# Hpowerv2.net
KiCad netlist of a schematic drawn in Altium Designer
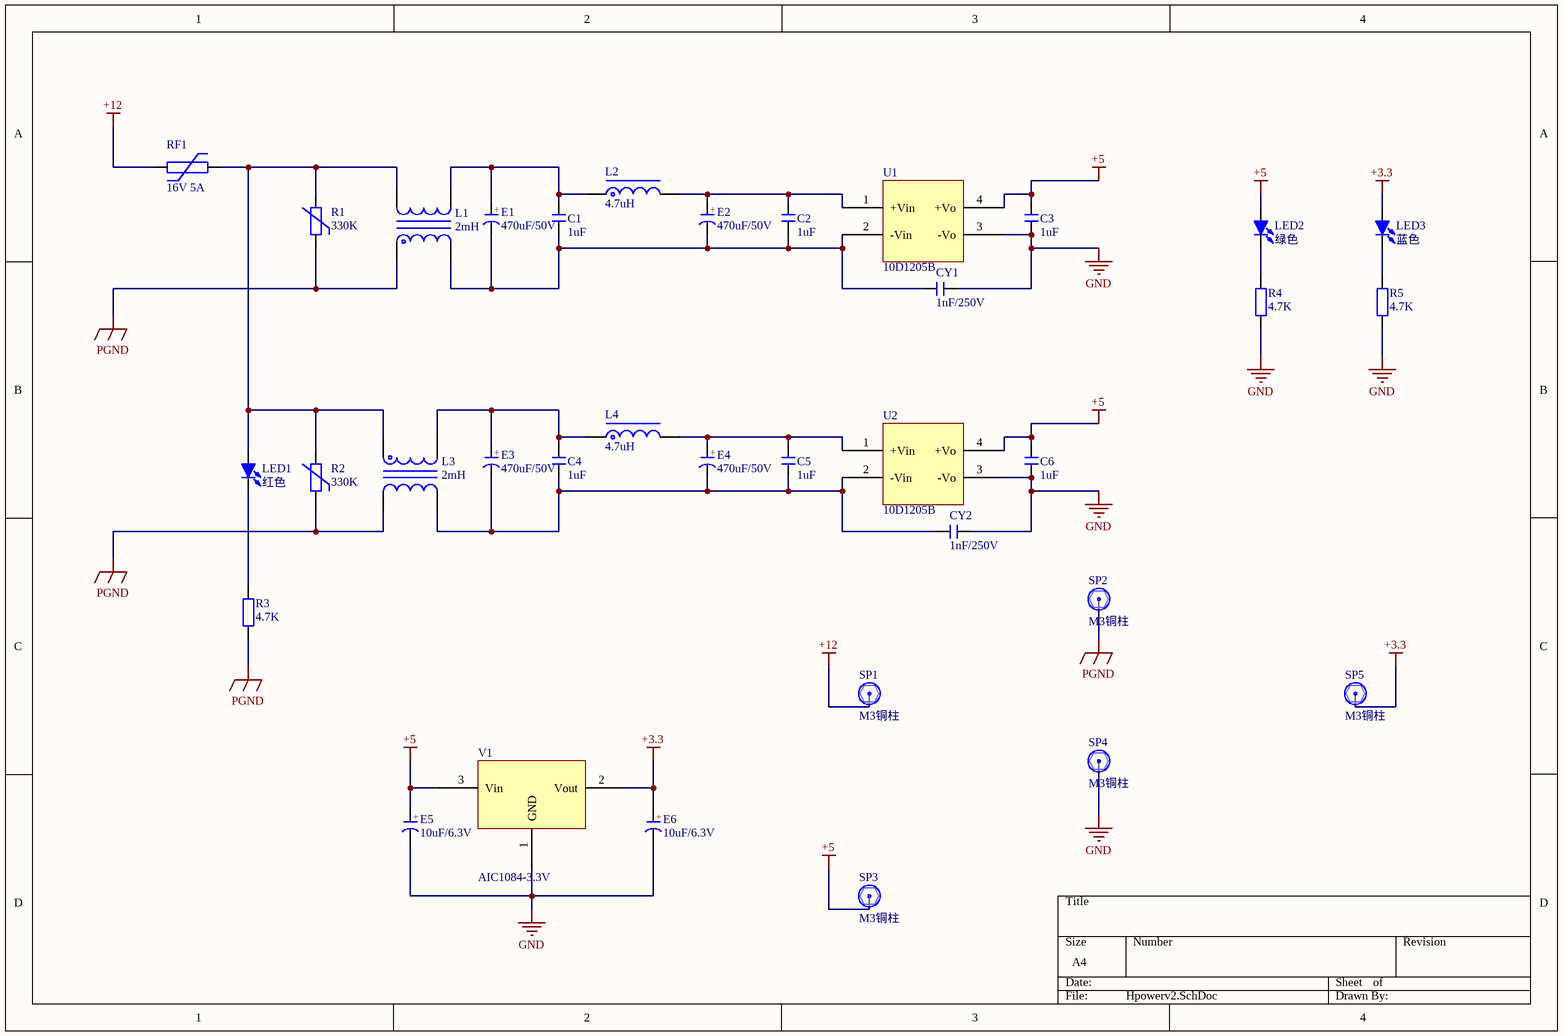
[diagram p0: Hpowerv2.SchDoc]

(export (version "E")
  (design (tool "Eeschema 10.0.6"))
  (components
    (comp (ref "C1")
      (value "1uF")
      (footprint "CC 2.2*5")
      (description "直插瓷片电容")
      (fields (field (name "版权归属") "源创客"))
      (libsource (lib "3.1   - 电阻-电容-电感") (part "C-CC"))
    )
    (comp (ref "C2")
      (value "1uF")
      (footprint "CC 2.2*5")
      (description "直插瓷片电容")
      (fields (field (name "版权归属") "源创客"))
      (libsource (lib "3.1   - 电阻-电容-电感") (part "C-CC"))
    )
    (comp (ref "C3")
      (value "1uF")
      (footprint "CC 2.2*5")
      (description "直插瓷片电容")
      (fields (field (name "版权归属") "源创客"))
      (libsource (lib "3.1   - 电阻-电容-电感") (part "C-CC"))
    )
    (comp (ref "C4")
      (value "1uF")
      (footprint "CC 2.2*5")
      (description "直插瓷片电容")
      (fields (field (name "版权归属") "源创客"))
      (libsource (lib "3.1   - 电阻-电容-电感") (part "C-CC"))
    )
    (comp (ref "C5")
      (value "1uF")
      (footprint "CC 2.2*5")
      (description "直插瓷片电容")
      (fields (field (name "版权归属") "源创客"))
      (libsource (lib "3.1   - 电阻-电容-电感") (part "C-CC"))
    )
    (comp (ref "C6")
      (value "1uF")
      (footprint "CC 2.2*5")
      (description "直插瓷片电容")
      (fields (field (name "版权归属") "源创客"))
      (libsource (lib "3.1   - 电阻-电容-电感") (part "C-CC"))
    )
    (comp (ref "CY1")
      (value "1nF/250V")
      (footprint "CY 7.5*10*4")
      (description "高压陶瓷电容，Y电容")
      (fields (field (name "版权归属") "源创客"))
      (libsource (lib "3.1   - 电阻-电容-电感") (part "C-CY"))
    )
    (comp (ref "CY2")
      (value "1nF/250V")
      (footprint "CY 7.5*10*4")
      (description "高压陶瓷电容，Y电容")
      (fields (field (name "版权归属") "源创客"))
      (libsource (lib "3.1   - 电阻-电容-电感") (part "C-CY"))
    )
    (comp (ref "E1")
      (value "470uF/50V")
      (footprint "CM G(12.5*13.5)")
      (description "贴片电解电容")
      (fields (field (name "版权归属") "源创客"))
      (libsource (lib "3.1   - 电阻-电容-电感") (part "C-CM"))
    )
    (comp (ref "E2")
      (value "470uF/50V")
      (footprint "CM G(12.5*13.5)")
      (description "贴片电解电容")
      (fields (field (name "版权归属") "源创客"))
      (libsource (lib "3.1   - 电阻-电容-电感") (part "C-CM"))
    )
    (comp (ref "E3")
      (value "470uF/50V")
      (footprint "CM G(12.5*13.5)")
      (description "贴片电解电容")
      (fields (field (name "版权归属") "源创客"))
      (libsource (lib "3.1   - 电阻-电容-电感") (part "C-CM"))
    )
    (comp (ref "E4")
      (value "470uF/50V")
      (footprint "CM G(12.5*13.5)")
      (description "贴片电解电容")
      (fields (field (name "版权归属") "源创客"))
      (libsource (lib "3.1   - 电阻-电容-电感") (part "C-CM"))
    )
    (comp (ref "E5")
      (value "10uF/6.3V")
      (footprint "CD A(3216)")
      (description "贴片钽电容")
      (fields (field (name "版权归属") "源创客"))
      (libsource (lib "3.1   - 电阻-电容-电感") (part "C-CD"))
    )
    (comp (ref "E6")
      (value "10uF/6.3V")
      (footprint "CD A(3216)")
      (description "贴片钽电容")
      (fields (field (name "版权归属") "源创客"))
      (libsource (lib "3.1   - 电阻-电容-电感") (part "C-CD"))
    )
    (comp (ref "L1")
      (value "2mH")
      (footprint "UU9.8")
      (description "共模电感")
      (fields (field (name "版权归属") "源创客"))
      (libsource (lib "") (part "L-CMC_1"))
    )
    (comp (ref "L2")
      (value "4.7uH")
      (footprint "NR5020")
      (description "NR磁胶电感")
      (fields (field (name "版权归属") "源创客"))
      (libsource (lib "3.1   - 电阻-电容-电感") (part "L-NR"))
    )
    (comp (ref "L3")
      (value "2mH")
      (footprint "UU9.8")
      (description "共模电感")
      (fields (field (name "版权归属") "源创客"))
      (libsource (lib "3.1   - 电阻-电容-电感") (part "L-CMC"))
    )
    (comp (ref "L4")
      (value "4.7uH")
      (footprint "NR5020")
      (description "NR磁胶电感")
      (fields (field (name "版权归属") "源创客"))
      (libsource (lib "3.1   - 电阻-电容-电感") (part "L-NR"))
    )
    (comp (ref "LED1")
      (value "红色")
      (footprint "LED 0603R")
      (description "贴片LED")
      (fields (field (name "版权归属") "源创客"))
      (libsource (lib "9.1   - LED") (part "LED-SMD"))
    )
    (comp (ref "LED2")
      (value "绿色")
      (footprint "LED 0603G")
      (description "贴片LED")
      (fields (field (name "版权归属") "源创客"))
      (libsource (lib "9.1   - LED") (part "LED-SMD"))
    )
    (comp (ref "LED3")
      (value "蓝色")
      (footprint "LED 0603B")
      (description "贴片LED")
      (fields (field (name "版权归属") "源创客"))
      (libsource (lib "9.1   - LED") (part "LED-SMD"))
    )
    (comp (ref "R1")
      (value "330K")
      (footprint "14D")
      (description "压敏电阻")
      (fields (field (name "版权归属") "源创客"))
      (libsource (lib "3.1   - 电阻-电容-电感") (part "R_VDR"))
    )
    (comp (ref "R2")
      (value "330K")
      (footprint "14D")
      (description "压敏电阻")
      (fields (field (name "版权归属") "源创客"))
      (libsource (lib "3.1   - 电阻-电容-电感") (part "R_VDR"))
    )
    (comp (ref "R3")
      (value "4.7K")
      (footprint "R 0603_M")
      (description "贴片电阻")
      (fields (field (name "版权归属") "源创客"))
      (libsource (lib "3.1   - 电阻-电容-电感") (part "R"))
    )
    (comp (ref "R4")
      (value "4.7K")
      (footprint "R 0603_M")
      (description "贴片电阻")
      (fields (field (name "版权归属") "源创客"))
      (libsource (lib "3.1   - 电阻-电容-电感") (part "R"))
    )
    (comp (ref "R5")
      (value "4.7K")
      (footprint "R 0603_M")
      (description "贴片电阻")
      (fields (field (name "版权归属") "源创客"))
      (libsource (lib "3.1   - 电阻-电容-电感") (part "R"))
    )
    (comp (ref "RF1")
      (value "16V 5A")
      (footprint "14D")
      (description "PPTC自恢复保险丝")
      (fields (field (name "版权归属") "源创客"))
      (libsource (lib "10.1 - 保险丝-晶振") (part "PPTC"))
    )
    (comp (ref "SP1")
      (value "M3铜柱")
      (footprint "M3x14_N")
      (description "铜柱")
      (fields (field (name "版权归属") "源创客"))
      (libsource (lib "15.1 - 未分类器件") (part "铜柱大焊盘"))
    )
    (comp (ref "SP2")
      (value "M3铜柱")
      (footprint "M3x14_N")
      (description "铜柱")
      (fields (field (name "版权归属") "源创客"))
      (libsource (lib "15.1 - 未分类器件") (part "铜柱大焊盘"))
    )
    (comp (ref "SP3")
      (value "M3铜柱")
      (footprint "M3x14_N")
      (description "铜柱")
      (fields (field (name "版权归属") "源创客"))
      (libsource (lib "15.1 - 未分类器件") (part "铜柱大焊盘"))
    )
    (comp (ref "SP4")
      (value "M3铜柱")
      (footprint "M3x14_N")
      (description "铜柱")
      (fields (field (name "版权归属") "源创客"))
      (libsource (lib "15.1 - 未分类器件") (part "铜柱大焊盘"))
    )
    (comp (ref "SP5")
      (value "M3铜柱")
      (footprint "M3x14_N")
      (description "铜柱")
      (fields (field (name "版权归属") "源创客"))
      (libsource (lib "15.1 - 未分类器件") (part "铜柱大焊盘"))
    )
    (comp (ref "U1")
      (value "10D1205B")
      (footprint "10D12B-10WDCDC")
      (description "DC-DC 12V转5V隔离降压模块")
      (libsource (lib "HLKPower") (part "10D1205B"))
    )
    (comp (ref "U2")
      (value "10D1205B")
      (footprint "10D12B-10WDCDC")
      (description "DC-DC 12V转5V隔离降压模块")
      (libsource (lib "HLKPower") (part "10D1205B"))
    )
    (comp (ref "V1")
      (value "AIC1084-3.3V")
      (footprint "TO263-3B")
      (description "大功率LDO")
      (libsource (lib "1.3   - 电源类芯片") (part "AIC1084"))
    )
  )
  (nets
    (net (code "1") (name "+3.3") (class "Default")
      (node (ref "E6") (pin "1") (pinfunction "A_1") (pintype "passive"))
      (node (ref "LED3") (pin "1") (pinfunction "A_1") (pintype "passive"))
      (node (ref "SP5") (pin "1") (pinfunction "1_1") (pintype "passive"))
      (node (ref "V1") (pin "2") (pinfunction "Vout_2") (pintype "passive"))
    )
    (net (code "2") (name "+5") (class "Default")
      (node (ref "C3") (pin "1") (pinfunction "1_1") (pintype "passive"))
      (node (ref "C6") (pin "1") (pinfunction "1_1") (pintype "passive"))
      (node (ref "E5") (pin "1") (pinfunction "A_1") (pintype "passive"))
      (node (ref "LED2") (pin "1") (pinfunction "A_1") (pintype "passive"))
      (node (ref "SP3") (pin "1") (pinfunction "1_1") (pintype "passive"))
      (node (ref "U1") (pin "4") (pinfunction "+Vo_4") (pintype "passive"))
      (node (ref "U2") (pin "4") (pinfunction "+Vo_4") (pintype "passive"))
      (node (ref "V1") (pin "3") (pinfunction "Vin_3") (pintype "passive"))
    )
    (net (code "3") (name "+12") (class "Default")
      (node (ref "RF1") (pin "1") (pinfunction "1_1") (pintype "passive"))
      (node (ref "SP1") (pin "1") (pinfunction "1_1") (pintype "passive"))
    )
    (net (code "4") (name "GND") (class "Default")
      (node (ref "C3") (pin "2") (pinfunction "2_2") (pintype "passive"))
      (node (ref "C6") (pin "2") (pinfunction "2_2") (pintype "passive"))
      (node (ref "CY1") (pin "2") (pinfunction "2_2") (pintype "passive"))
      (node (ref "CY2") (pin "2") (pinfunction "2_2") (pintype "passive"))
      (node (ref "E5") (pin "2") (pinfunction "K_2") (pintype "passive"))
      (node (ref "E6") (pin "2") (pinfunction "K_2") (pintype "passive"))
      (node (ref "R4") (pin "1") (pinfunction "1_1") (pintype "passive"))
      (node (ref "R5") (pin "1") (pinfunction "1_1") (pintype "passive"))
      (node (ref "SP4") (pin "1") (pinfunction "1_1") (pintype "passive"))
      (node (ref "U1") (pin "3") (pinfunction "-Vo_3") (pintype "passive"))
      (node (ref "U2") (pin "3") (pinfunction "-Vo_3") (pintype "passive"))
      (node (ref "V1") (pin "1") (pinfunction "GND_1") (pintype "passive"))
    )
    (net (code "5") (name "Net-(E1-A)") (class "Default")
      (node (ref "C1") (pin "1") (pinfunction "1_1") (pintype "passive"))
      (node (ref "E1") (pin "1") (pinfunction "A_1") (pintype "passive"))
      (node (ref "L1") (pin "3") (pinfunction "3_3") (pintype "passive"))
      (node (ref "L2") (pin "1") (pinfunction "1_1") (pintype "passive"))
    )
    (net (code "6") (name "Net-(E1-K)") (class "Default")
      (node (ref "C1") (pin "2") (pinfunction "2_2") (pintype "passive"))
      (node (ref "C2") (pin "2") (pinfunction "2_2") (pintype "passive"))
      (node (ref "CY1") (pin "1") (pinfunction "1_1") (pintype "passive"))
      (node (ref "E1") (pin "2") (pinfunction "K_2") (pintype "passive"))
      (node (ref "E2") (pin "2") (pinfunction "K_2") (pintype "passive"))
      (node (ref "L1") (pin "2") (pinfunction "2_2") (pintype "passive"))
      (node (ref "U1") (pin "2") (pinfunction "-Vin_2") (pintype "passive"))
    )
    (net (code "7") (name "Net-(E2-A)") (class "Default")
      (node (ref "C2") (pin "1") (pinfunction "1_1") (pintype "passive"))
      (node (ref "E2") (pin "1") (pinfunction "A_1") (pintype "passive"))
      (node (ref "L2") (pin "2") (pinfunction "2_2") (pintype "passive"))
      (node (ref "U1") (pin "1") (pinfunction "+Vin_1") (pintype "passive"))
    )
    (net (code "8") (name "Net-(E3-A)") (class "Default")
      (node (ref "C4") (pin "1") (pinfunction "1_1") (pintype "passive"))
      (node (ref "E3") (pin "1") (pinfunction "A_1") (pintype "passive"))
      (node (ref "L3") (pin "2") (pinfunction "2_2") (pintype "passive"))
      (node (ref "L4") (pin "1") (pinfunction "1_1") (pintype "passive"))
    )
    (net (code "9") (name "Net-(E3-K)") (class "Default")
      (node (ref "C4") (pin "2") (pinfunction "2_2") (pintype "passive"))
      (node (ref "C5") (pin "2") (pinfunction "2_2") (pintype "passive"))
      (node (ref "CY2") (pin "1") (pinfunction "1_1") (pintype "passive"))
      (node (ref "E3") (pin "2") (pinfunction "K_2") (pintype "passive"))
      (node (ref "E4") (pin "2") (pinfunction "K_2") (pintype "passive"))
      (node (ref "L3") (pin "3") (pinfunction "3_3") (pintype "passive"))
      (node (ref "U2") (pin "2") (pinfunction "-Vin_2") (pintype "passive"))
    )
    (net (code "10") (name "Net-(E4-A)") (class "Default")
      (node (ref "C5") (pin "1") (pinfunction "1_1") (pintype "passive"))
      (node (ref "E4") (pin "1") (pinfunction "A_1") (pintype "passive"))
      (node (ref "L4") (pin "2") (pinfunction "2_2") (pintype "passive"))
      (node (ref "U2") (pin "1") (pinfunction "+Vin_1") (pintype "passive"))
    )
    (net (code "11") (name "Net-(LED1-A)") (class "Default")
      (node (ref "L1") (pin "4") (pinfunction "4_4") (pintype "passive"))
      (node (ref "L3") (pin "1") (pinfunction "1_1") (pintype "passive"))
      (node (ref "LED1") (pin "1") (pinfunction "A_1") (pintype "passive"))
      (node (ref "R1") (pin "2") (pinfunction "2_2") (pintype "passive"))
      (node (ref "R2") (pin "2") (pinfunction "2_2") (pintype "passive"))
      (node (ref "RF1") (pin "2") (pinfunction "2_2") (pintype "passive"))
    )
    (net (code "12") (name "Net-(LED1-K)") (class "Default")
      (node (ref "LED1") (pin "2") (pinfunction "K_2") (pintype "passive"))
      (node (ref "R3") (pin "2") (pinfunction "2_2") (pintype "passive"))
    )
    (net (code "13") (name "Net-(LED2-K)") (class "Default")
      (node (ref "LED2") (pin "2") (pinfunction "K_2") (pintype "passive"))
      (node (ref "R4") (pin "2") (pinfunction "2_2") (pintype "passive"))
    )
    (net (code "14") (name "Net-(LED3-K)") (class "Default")
      (node (ref "LED3") (pin "2") (pinfunction "K_2") (pintype "passive"))
      (node (ref "R5") (pin "2") (pinfunction "2_2") (pintype "passive"))
    )
    (net (code "15") (name "PGND") (class "Default")
      (node (ref "L1") (pin "1") (pinfunction "1_1") (pintype "passive"))
      (node (ref "L3") (pin "4") (pinfunction "4_4") (pintype "passive"))
      (node (ref "R1") (pin "1") (pinfunction "1_1") (pintype "passive"))
      (node (ref "R2") (pin "1") (pinfunction "1_1") (pintype "passive"))
      (node (ref "R3") (pin "1") (pinfunction "1_1") (pintype "passive"))
      (node (ref "SP2") (pin "1") (pinfunction "1_1") (pintype "passive"))
    )
  )
)
